# SCH_STAYAW_0_3_2024-05-15.net
KiCad netlist of a schematic drawn in EasyEDA
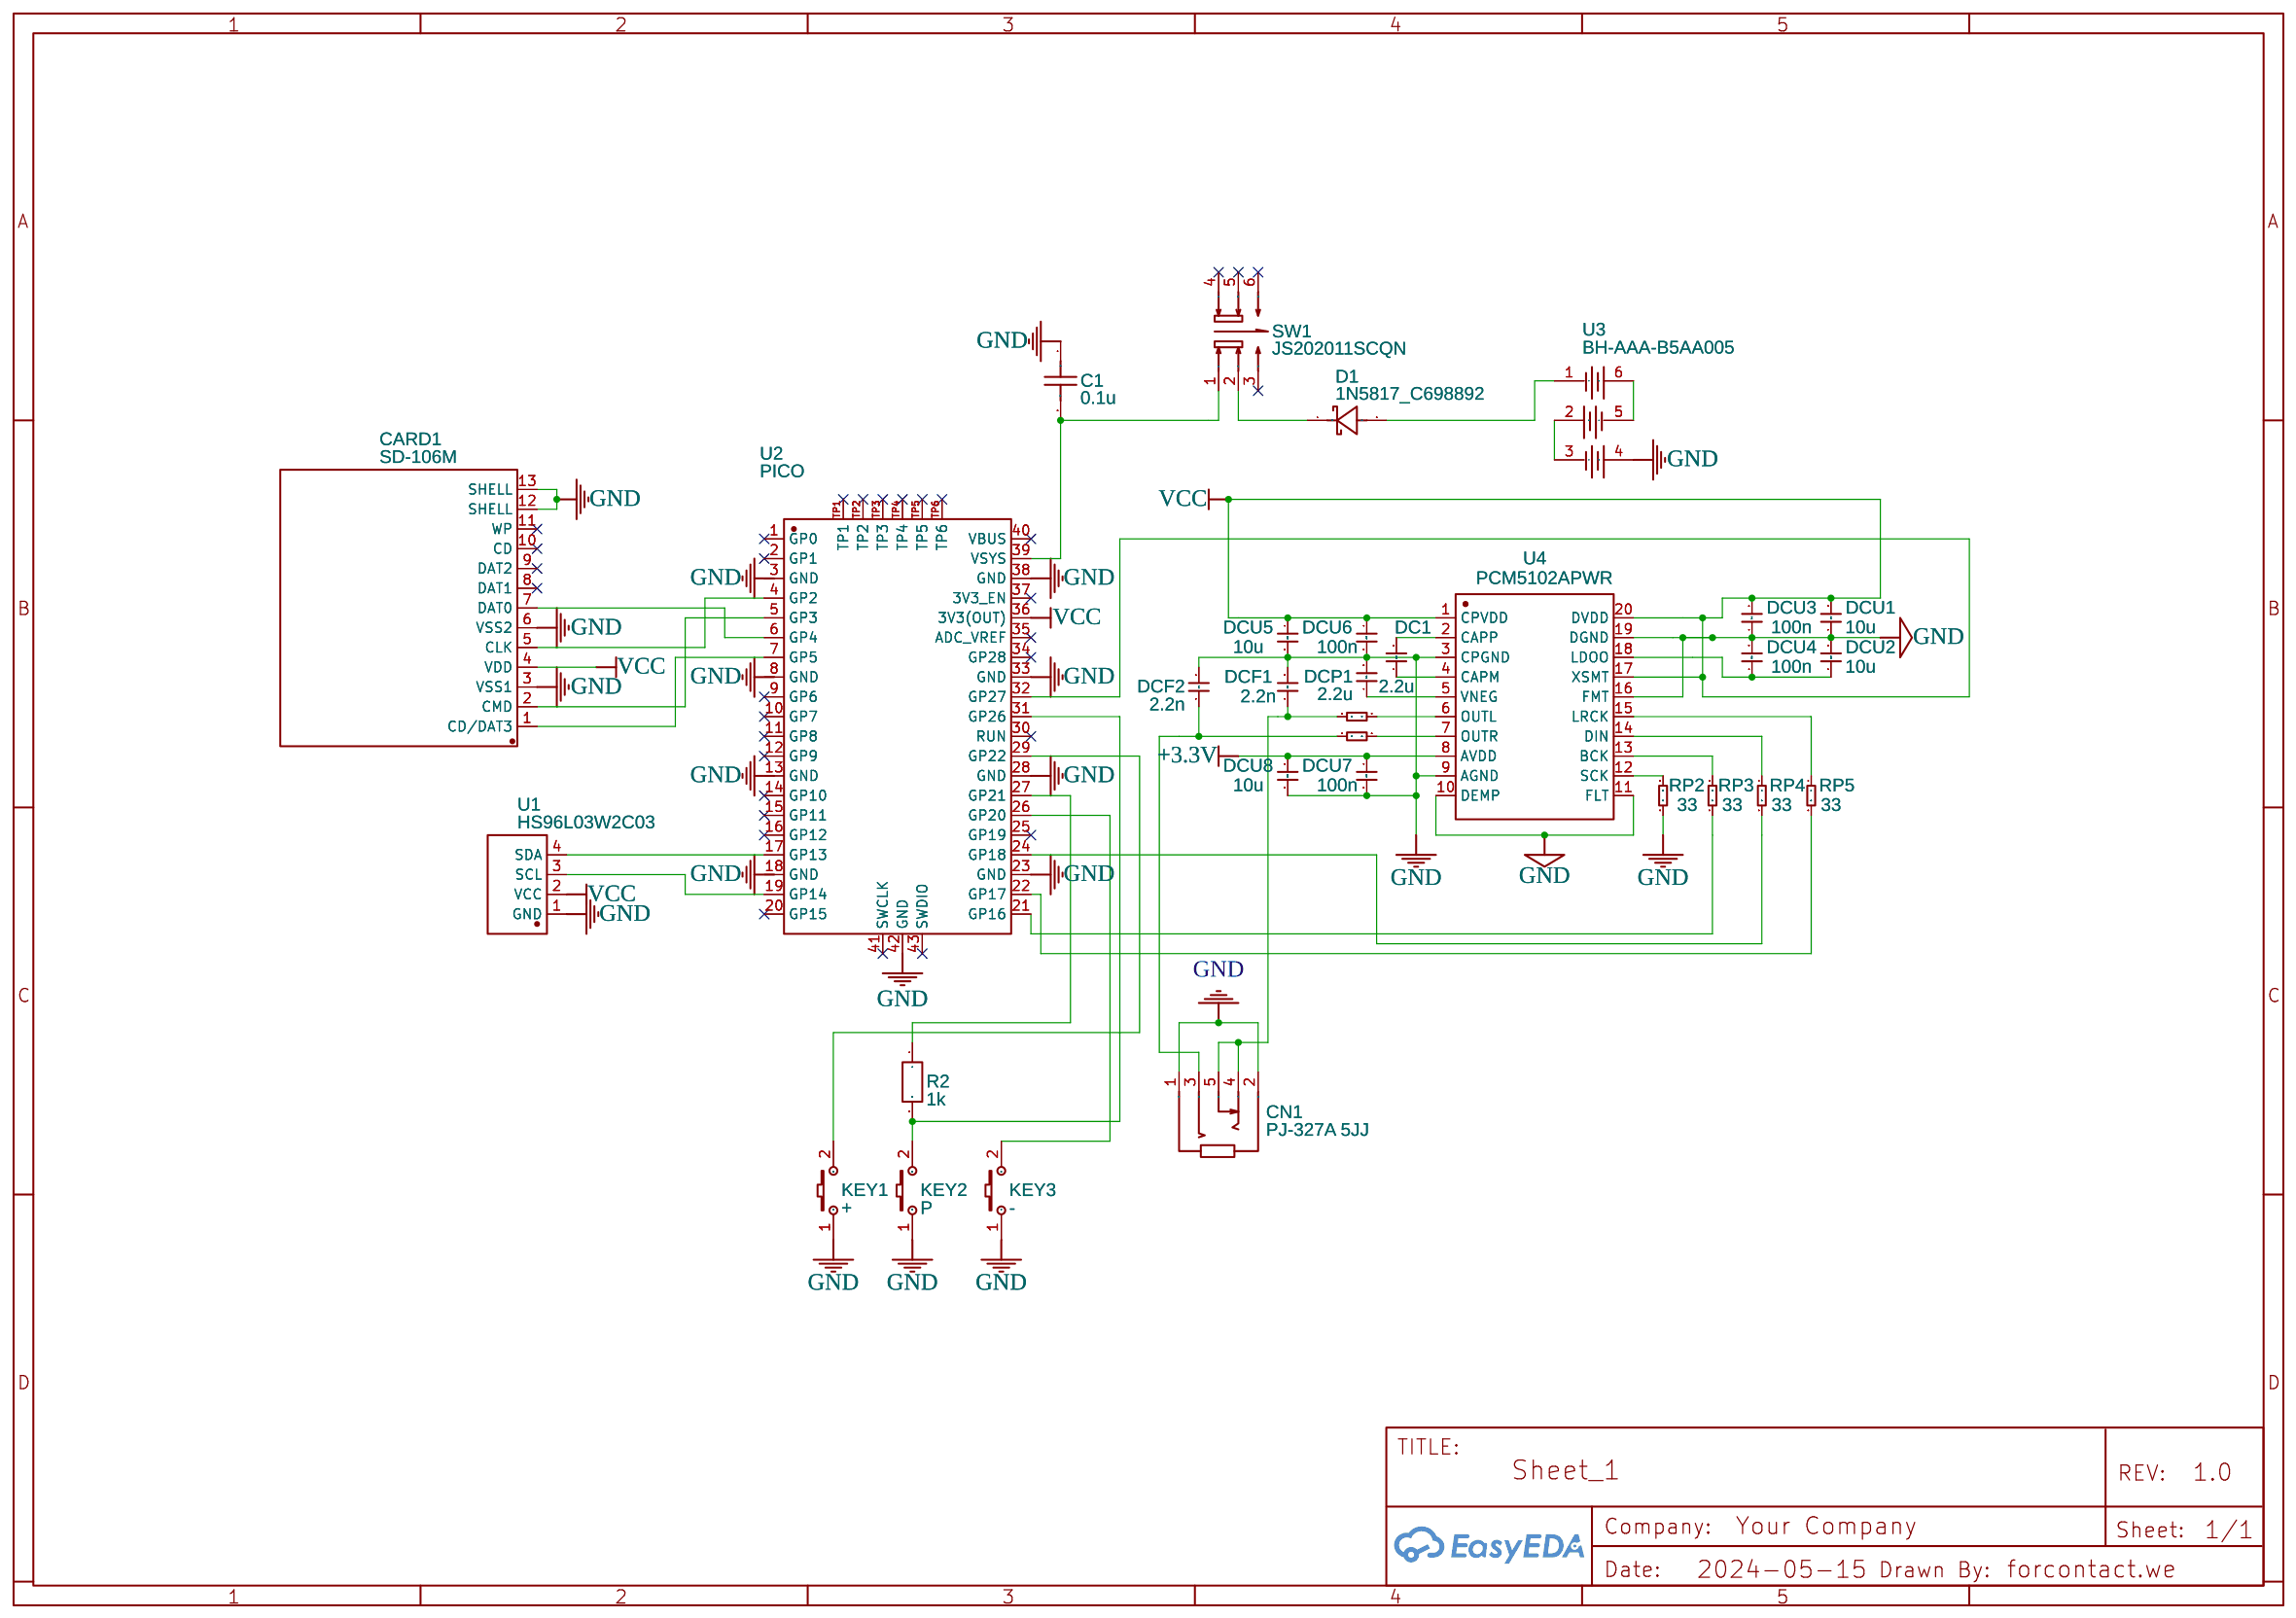
[diagram p0: schematic sheet]

(export (version "E")
  (design (tool "Eeschema 10.0.6"))
  (components
    (comp (ref "C1") (value "0.1u") (libsource (lib "") (part "C_0603_US")))
    (comp (ref "CARD1")
      (value "SD-106M")
      (fields (field (name "Manufacturer") "XUNPU(讯普)"))
      (libsource (lib "") (part "SD-106M"))
    )
    (comp (ref "CN1")
      (value "PJ-327A 5JJ")
      (fields (field (name "Manufacturer") "SHOU HAN(首韩)"))
      (libsource (lib "") (part "PJ-327A 5JJ"))
    )
    (comp (ref "D1")
      (value "1N5817_C698892")
      (fields (field (name "Manufacturer Part") "1N5817") (field (name "Manufacturer") "YANGJIE(扬杰)"))
      (libsource (lib "") (part "1N5817_C698892"))
    )
    (comp (ref "DC1")
      (value "2.2u")
      (fields (field (name "Manufacturer Part") "CL21B105KBFNNNE") (field (name "Manufacturer") "SAMSUNG"))
      (libsource (lib "") (part "Cap_0603_US_4"))
    )
    (comp (ref "DCF1")
      (value "2.2n")
      (fields (field (name "Manufacturer Part") "CL21A106KAYNNNE") (field (name "Manufacturer") "SAMSUNG"))
      (libsource (lib "") (part "Cap_0603_US_3"))
    )
    (comp (ref "DCF2")
      (value "2.2n")
      (fields (field (name "Manufacturer Part") "CL21A106KAYNNNE") (field (name "Manufacturer") "SAMSUNG"))
      (libsource (lib "") (part "Cap_0603_US_3"))
    )
    (comp (ref "DCP1")
      (value "2.2u")
      (fields (field (name "Manufacturer Part") "CL21B105KBFNNNE") (field (name "Manufacturer") "SAMSUNG"))
      (libsource (lib "") (part "Cap_0603_US_1"))
    )
    (comp (ref "DCU1")
      (value "10u")
      (fields (field (name "Manufacturer Part") "CL21A106KAYNNNE") (field (name "Manufacturer") "SAMSUNG"))
      (libsource (lib "") (part "Cap_0603_US"))
    )
    (comp (ref "DCU2")
      (value "10u")
      (fields (field (name "Manufacturer Part") "CL21A106KAYNNNE") (field (name "Manufacturer") "SAMSUNG"))
      (libsource (lib "") (part "Cap_0603_US"))
    )
    (comp (ref "DCU3")
      (value "100n")
      (fields (field (name "Manufacturer Part") "CL21A106KAYNNNE") (field (name "Manufacturer") "SAMSUNG"))
      (libsource (lib "") (part "Cap_0603_US"))
    )
    (comp (ref "DCU4")
      (value "100n")
      (fields (field (name "Manufacturer Part") "CL21A106KAYNNNE") (field (name "Manufacturer") "SAMSUNG"))
      (libsource (lib "") (part "Cap_0603_US"))
    )
    (comp (ref "DCU5")
      (value "10u")
      (fields (field (name "Manufacturer Part") "CL21A106KAYNNNE") (field (name "Manufacturer") "SAMSUNG"))
      (libsource (lib "") (part "Cap_0603_US_2"))
    )
    (comp (ref "DCU6")
      (value "100n")
      (fields (field (name "Manufacturer Part") "CL21A106KAYNNNE") (field (name "Manufacturer") "SAMSUNG"))
      (libsource (lib "") (part "Cap_0603_US_2"))
    )
    (comp (ref "DCU7")
      (value "100n")
      (fields (field (name "Manufacturer Part") "CL21A106KAYNNNE") (field (name "Manufacturer") "SAMSUNG"))
      (libsource (lib "") (part "Cap_0603_US_2"))
    )
    (comp (ref "DCU8")
      (value "10u")
      (fields (field (name "Manufacturer Part") "CL21A106KAYNNNE") (field (name "Manufacturer") "SAMSUNG"))
      (libsource (lib "") (part "Cap_0603_US_2"))
    )
    (comp (ref "DR1")
      (value "470")
      (fields (field (name "Manufacturer Part") "?"))
      (libsource (lib "") (part "Res_0603(1/10W)_EU_1"))
    )
    (comp (ref "DR2")
      (value "470")
      (fields (field (name "Manufacturer Part") "?"))
      (libsource (lib "") (part "Res_0603(1/10W)_EU_1"))
    )
    (comp (ref "KEY1")
      (value "+")
      (fields (field (name "Manufacturer Part") "K2-1107ST-A4SW-06"))
      (libsource (lib "") (part "K2-3.6×6.1_SMD"))
    )
    (comp (ref "KEY2")
      (value "P")
      (fields (field (name "Manufacturer Part") "K2-1107ST-A4SW-06"))
      (libsource (lib "") (part "K2-3.6×6.1_SMD"))
    )
    (comp (ref "KEY3")
      (value "-")
      (fields (field (name "Manufacturer Part") "K2-1107ST-A4SW-06"))
      (libsource (lib "") (part "K2-3.6×6.1_SMD"))
    )
    (comp (ref "R2") (value "1k") (libsource (lib "") (part "R_0603_EU")))
    (comp (ref "RP2")
      (value "33")
      (fields (field (name "Manufacturer Part") "?"))
      (libsource (lib "") (part "Res_0603(1/10W)_EU"))
    )
    (comp (ref "RP3")
      (value "33")
      (fields (field (name "Manufacturer Part") "?"))
      (libsource (lib "") (part "Res_0603(1/10W)_EU"))
    )
    (comp (ref "RP4")
      (value "33")
      (fields (field (name "Manufacturer Part") "?"))
      (libsource (lib "") (part "Res_0603(1/10W)_EU"))
    )
    (comp (ref "RP5")
      (value "33")
      (fields (field (name "Manufacturer Part") "?"))
      (libsource (lib "") (part "Res_0603(1/10W)_EU"))
    )
    (comp (ref "SW1")
      (value "JS202011SCQN")
      (fields (field (name "Manufacturer") "C&K"))
      (libsource (lib "") (part "JS202011SCQN"))
    )
    (comp (ref "U1")
      (value "HS96L03W2C03")
      (fields (field (name "Manufacturer") "HS(汉昇)"))
      (libsource (lib "") (part "HS96L03W2C03"))
    )
    (comp (ref "U2")
      (value "PICO")
      (fields (field (name "Manufacturer") "Raspberry Pi(树莓派)"))
      (libsource (lib "") (part "PICO"))
    )
    (comp (ref "U3")
      (value "BH-AAA-B5AA005")
      (fields (field (name "Manufacturer") "MYOUNG(美阳)"))
      (libsource (lib "") (part "BH-AAA-B5AA005"))
    )
    (comp (ref "U4")
      (value "PCM5102APWR")
      (fields (field (name "Manufacturer") "TI"))
      (libsource (lib "") (part "PCM5102APWR"))
    )
  )
  (nets
    (net (code "1") (name "+3.3V") (class "Default")
      (node (ref "DCU7") (pin "1") (pinfunction "1_1") (pintype "unspecified"))
      (node (ref "DCU8") (pin "1") (pinfunction "1_1") (pintype "unspecified"))
      (node (ref "U4") (pin "8") (pinfunction "AVDD_8") (pintype "unspecified"))
    )
    (net (code "2") (name "GND") (class "Default")
      (node (ref "C1") (pin "1") (pinfunction "1_1") (pintype "unspecified"))
      (node (ref "CARD1") (pin "12") (pinfunction "SHELL_12") (pintype "unspecified"))
      (node (ref "CARD1") (pin "13") (pinfunction "SHELL_13") (pintype "unspecified"))
      (node (ref "CARD1") (pin "3") (pinfunction "VSS1_3") (pintype "unspecified"))
      (node (ref "CARD1") (pin "6") (pinfunction "VSS2_6") (pintype "unspecified"))
      (node (ref "CN1") (pin "1") (pinfunction "1_1") (pintype "unspecified"))
      (node (ref "CN1") (pin "2") (pinfunction "2_2") (pintype "unspecified"))
      (node (ref "DCF1") (pin "2") (pinfunction "2_2") (pintype "unspecified"))
      (node (ref "DCF2") (pin "2") (pinfunction "2_2") (pintype "unspecified"))
      (node (ref "DCP1") (pin "2") (pinfunction "2_2") (pintype "unspecified"))
      (node (ref "DCU1") (pin "1") (pinfunction "1_1") (pintype "unspecified"))
      (node (ref "DCU2") (pin "2") (pinfunction "2_2") (pintype "unspecified"))
      (node (ref "DCU3") (pin "1") (pinfunction "1_1") (pintype "unspecified"))
      (node (ref "DCU4") (pin "2") (pinfunction "2_2") (pintype "unspecified"))
      (node (ref "DCU5") (pin "2") (pinfunction "2_2") (pintype "unspecified"))
      (node (ref "DCU6") (pin "2") (pinfunction "2_2") (pintype "unspecified"))
      (node (ref "DCU7") (pin "2") (pinfunction "2_2") (pintype "unspecified"))
      (node (ref "DCU8") (pin "2") (pinfunction "2_2") (pintype "unspecified"))
      (node (ref "KEY1") (pin "1") (pinfunction "1_1") (pintype "unspecified"))
      (node (ref "KEY2") (pin "1") (pinfunction "1_1") (pintype "unspecified"))
      (node (ref "KEY3") (pin "1") (pinfunction "1_1") (pintype "unspecified"))
      (node (ref "RP2") (pin "2") (pinfunction "2_2") (pintype "unspecified"))
      (node (ref "U1") (pin "1") (pinfunction "GND_1") (pintype "unspecified"))
      (node (ref "U2") (pin "13") (pinfunction "GND_13") (pintype "unspecified"))
      (node (ref "U2") (pin "18") (pinfunction "GND_18") (pintype "unspecified"))
      (node (ref "U2") (pin "23") (pinfunction "GND_23") (pintype "unspecified"))
      (node (ref "U2") (pin "28") (pinfunction "GND_28") (pintype "unspecified"))
      (node (ref "U2") (pin "3") (pinfunction "GND_3") (pintype "unspecified"))
      (node (ref "U2") (pin "33") (pinfunction "GND_33") (pintype "unspecified"))
      (node (ref "U2") (pin "38") (pinfunction "GND_38") (pintype "unspecified"))
      (node (ref "U2") (pin "42") (pinfunction "GND_42") (pintype "unspecified"))
      (node (ref "U2") (pin "8") (pinfunction "GND_8") (pintype "unspecified"))
      (node (ref "U3") (pin "4") (pinfunction "+_4") (pintype "input"))
      (node (ref "U4") (pin "10") (pinfunction "DEMP_10") (pintype "unspecified"))
      (node (ref "U4") (pin "11") (pinfunction "FLT_11") (pintype "unspecified"))
      (node (ref "U4") (pin "16") (pinfunction "FMT_16") (pintype "unspecified"))
      (node (ref "U4") (pin "19") (pinfunction "DGND_19") (pintype "unspecified"))
      (node (ref "U4") (pin "3") (pinfunction "CPGND_3") (pintype "unspecified"))
      (node (ref "U4") (pin "9") (pinfunction "AGND_9") (pintype "unspecified"))
    )
    (net (code "3") (name "Net-(CARD1-CD{slash}DAT3)") (class "Default")
      (node (ref "CARD1") (pin "1") (pinfunction "CD/DAT3_1") (pintype "unspecified"))
      (node (ref "U2") (pin "7") (pinfunction "GP5_7") (pintype "unspecified"))
    )
    (net (code "4") (name "Net-(CARD1-CLK)") (class "Default")
      (node (ref "CARD1") (pin "5") (pinfunction "CLK_5") (pintype "unspecified"))
      (node (ref "U2") (pin "4") (pinfunction "GP2_4") (pintype "unspecified"))
    )
    (net (code "5") (name "Net-(CARD1-CMD)") (class "Default")
      (node (ref "CARD1") (pin "2") (pinfunction "CMD_2") (pintype "unspecified"))
      (node (ref "U2") (pin "5") (pinfunction "GP3_5") (pintype "unspecified"))
    )
    (net (code "6") (name "Net-(CARD1-DAT0)") (class "Default")
      (node (ref "CARD1") (pin "7") (pinfunction "DAT0_7") (pintype "unspecified"))
      (node (ref "U2") (pin "6") (pinfunction "GP4_6") (pintype "unspecified"))
    )
    (net (code "7") (name "Net-(CN1-Pad3)") (class "Default")
      (node (ref "CN1") (pin "3") (pinfunction "3_3") (pintype "unspecified"))
      (node (ref "DCF2") (pin "1") (pinfunction "1_1") (pintype "unspecified"))
      (node (ref "DR1") (pin "1") (pinfunction "1_1") (pintype "unspecified"))
    )
    (net (code "8") (name "Net-(CN1-Pad4)") (class "Default")
      (node (ref "CN1") (pin "4") (pinfunction "4_4") (pintype "unspecified"))
      (node (ref "CN1") (pin "5") (pinfunction "5_5") (pintype "unspecified"))
      (node (ref "DCF1") (pin "1") (pinfunction "1_1") (pintype "unspecified"))
      (node (ref "DR2") (pin "1") (pinfunction "1_1") (pintype "unspecified"))
    )
    (net (code "9") (name "Net-(D1-Pad1)") (class "Default")
      (node (ref "D1") (pin "1") (pinfunction "1_1") (pintype "unspecified"))
      (node (ref "SW1") (pin "2") (pinfunction "2_2") (pintype "unspecified"))
    )
    (net (code "10") (name "Net-(D1-Pad2)") (class "Default")
      (node (ref "D1") (pin "2") (pinfunction "2_2") (pintype "unspecified"))
      (node (ref "U3") (pin "1") (pinfunction "-_1") (pintype "input"))
    )
    (net (code "11") (name "Net-(U1-SCL)") (class "Default")
      (node (ref "U1") (pin "3") (pinfunction "SCL_3") (pintype "unspecified"))
      (node (ref "U2") (pin "19") (pinfunction "GP14_19") (pintype "unspecified"))
    )
    (net (code "12") (name "Net-(U1-SDA)") (class "Default")
      (node (ref "U1") (pin "4") (pinfunction "SDA_4") (pintype "unspecified"))
      (node (ref "U2") (pin "17") (pinfunction "GP13_17") (pintype "unspecified"))
    )
    (net (code "13") (name "Net-(U2-GP16)") (class "Default")
      (node (ref "RP3") (pin "2") (pinfunction "2_2") (pintype "unspecified"))
      (node (ref "U2") (pin "21") (pinfunction "GP16_21") (pintype "unspecified"))
    )
    (net (code "14") (name "Net-(U2-GP17)") (class "Default")
      (node (ref "RP5") (pin "2") (pinfunction "2_2") (pintype "unspecified"))
      (node (ref "U2") (pin "22") (pinfunction "GP17_22") (pintype "unspecified"))
    )
    (net (code "15") (name "Net-(U2-GP18)") (class "Default")
      (node (ref "RP4") (pin "2") (pinfunction "2_2") (pintype "unspecified"))
      (node (ref "U2") (pin "24") (pinfunction "GP18_24") (pintype "unspecified"))
    )
    (net (code "16") (name "Net-(U2-GP20)") (class "Default")
      (node (ref "KEY3") (pin "2") (pinfunction "2_2") (pintype "unspecified"))
      (node (ref "U2") (pin "26") (pinfunction "GP20_26") (pintype "unspecified"))
    )
    (net (code "17") (name "Net-(U2-GP21)") (class "Default")
      (node (ref "R2") (pin "1") (pinfunction "1_1") (pintype "unspecified"))
      (node (ref "U2") (pin "27") (pinfunction "GP21_27") (pintype "unspecified"))
    )
    (net (code "18") (name "Net-(U2-GP22)") (class "Default")
      (node (ref "KEY1") (pin "2") (pinfunction "2_2") (pintype "unspecified"))
      (node (ref "U2") (pin "29") (pinfunction "GP22_29") (pintype "unspecified"))
    )
    (net (code "19") (name "Net-(U2-GP26)") (class "Default")
      (node (ref "KEY2") (pin "2") (pinfunction "2_2") (pintype "unspecified"))
      (node (ref "R2") (pin "2") (pinfunction "2_2") (pintype "unspecified"))
      (node (ref "U2") (pin "31") (pinfunction "GP26_31") (pintype "unspecified"))
    )
    (net (code "20") (name "Net-(U2-VSYS)") (class "Default")
      (node (ref "C1") (pin "2") (pinfunction "2_2") (pintype "unspecified"))
      (node (ref "SW1") (pin "1") (pinfunction "1_1") (pintype "unspecified"))
      (node (ref "U2") (pin "39") (pinfunction "VSYS_39") (pintype "unspecified"))
    )
    (net (code "21") (name "Net-(U3-+-Pad2)") (class "Default")
      (node (ref "U3") (pin "2") (pinfunction "+_2") (pintype "input"))
      (node (ref "U3") (pin "3") (pinfunction "-_3") (pintype "input"))
    )
    (net (code "22") (name "Net-(U3-+-Pad6)") (class "Default")
      (node (ref "U3") (pin "5") (pinfunction "-_5") (pintype "input"))
      (node (ref "U3") (pin "6") (pinfunction "+_6") (pintype "input"))
    )
    (net (code "23") (name "Net-(U4-BCK)") (class "Default")
      (node (ref "RP3") (pin "1") (pinfunction "1_1") (pintype "unspecified"))
      (node (ref "U4") (pin "13") (pinfunction "BCK_13") (pintype "unspecified"))
    )
    (net (code "24") (name "Net-(U4-CAPM)") (class "Default")
      (node (ref "DC1") (pin "1") (pinfunction "1_1") (pintype "unspecified"))
      (node (ref "U4") (pin "4") (pinfunction "CAPM_4") (pintype "unspecified"))
    )
    (net (code "25") (name "Net-(U4-CAPP)") (class "Default")
      (node (ref "DC1") (pin "2") (pinfunction "2_2") (pintype "unspecified"))
      (node (ref "U4") (pin "2") (pinfunction "CAPP_2") (pintype "unspecified"))
    )
    (net (code "26") (name "Net-(U4-DIN)") (class "Default")
      (node (ref "RP4") (pin "1") (pinfunction "1_1") (pintype "unspecified"))
      (node (ref "U4") (pin "14") (pinfunction "DIN_14") (pintype "unspecified"))
    )
    (net (code "27") (name "Net-(U4-LDOO)") (class "Default")
      (node (ref "DCU2") (pin "1") (pinfunction "1_1") (pintype "unspecified"))
      (node (ref "DCU4") (pin "1") (pinfunction "1_1") (pintype "unspecified"))
      (node (ref "U4") (pin "18") (pinfunction "LDOO_18") (pintype "unspecified"))
    )
    (net (code "28") (name "Net-(U4-LRCK)") (class "Default")
      (node (ref "RP5") (pin "1") (pinfunction "1_1") (pintype "unspecified"))
      (node (ref "U4") (pin "15") (pinfunction "LRCK_15") (pintype "unspecified"))
    )
    (net (code "29") (name "Net-(U4-OUTL)") (class "Default")
      (node (ref "DR2") (pin "2") (pinfunction "2_2") (pintype "unspecified"))
      (node (ref "U4") (pin "6") (pinfunction "OUTL_6") (pintype "unspecified"))
    )
    (net (code "30") (name "Net-(U4-OUTR)") (class "Default")
      (node (ref "DR1") (pin "2") (pinfunction "2_2") (pintype "unspecified"))
      (node (ref "U4") (pin "7") (pinfunction "OUTR_7") (pintype "unspecified"))
    )
    (net (code "31") (name "Net-(U4-SCK)") (class "Default")
      (node (ref "RP2") (pin "1") (pinfunction "1_1") (pintype "unspecified"))
      (node (ref "U4") (pin "12") (pinfunction "SCK_12") (pintype "unspecified"))
    )
    (net (code "32") (name "Net-(U4-VNEG)") (class "Default")
      (node (ref "DCP1") (pin "1") (pinfunction "1_1") (pintype "unspecified"))
      (node (ref "U4") (pin "5") (pinfunction "VNEG_5") (pintype "unspecified"))
    )
    (net (code "33") (name "VCC") (class "Default")
      (node (ref "CARD1") (pin "4") (pinfunction "VDD_4") (pintype "unspecified"))
      (node (ref "DCU1") (pin "2") (pinfunction "2_2") (pintype "unspecified"))
      (node (ref "DCU3") (pin "2") (pinfunction "2_2") (pintype "unspecified"))
      (node (ref "DCU5") (pin "1") (pinfunction "1_1") (pintype "unspecified"))
      (node (ref "DCU6") (pin "1") (pinfunction "1_1") (pintype "unspecified"))
      (node (ref "U1") (pin "2") (pinfunction "VCC_2") (pintype "unspecified"))
      (node (ref "U2") (pin "32") (pinfunction "GP27_32") (pintype "unspecified"))
      (node (ref "U2") (pin "36") (pinfunction "3V3(OUT)_36") (pintype "unspecified"))
      (node (ref "U4") (pin "1") (pinfunction "CPVDD_1") (pintype "unspecified"))
      (node (ref "U4") (pin "17") (pinfunction "XSMT_17") (pintype "unspecified"))
      (node (ref "U4") (pin "20") (pinfunction "DVDD_20") (pintype "unspecified"))
    )
    (net (code "34") (name "unconnected-(CARD1-CD-Pad10)") (class "Default")
      (node (ref "CARD1") (pin "10") (pinfunction "CD_10") (pintype "unspecified+no_connect"))
    )
    (net (code "35") (name "unconnected-(CARD1-DAT1-Pad8)") (class "Default")
      (node (ref "CARD1") (pin "8") (pinfunction "DAT1_8") (pintype "unspecified+no_connect"))
    )
    (net (code "36") (name "unconnected-(CARD1-DAT2-Pad9)") (class "Default")
      (node (ref "CARD1") (pin "9") (pinfunction "DAT2_9") (pintype "unspecified+no_connect"))
    )
    (net (code "37") (name "unconnected-(CARD1-WP-Pad11)") (class "Default")
      (node (ref "CARD1") (pin "11") (pinfunction "WP_11") (pintype "unspecified+no_connect"))
    )
    (net (code "38") (name "unconnected-(SW1-Pad3)") (class "Default")
      (node (ref "SW1") (pin "3") (pinfunction "3_3") (pintype "unspecified+no_connect"))
    )
    (net (code "39") (name "unconnected-(SW1-Pad4)") (class "Default")
      (node (ref "SW1") (pin "4") (pinfunction "4_4") (pintype "unspecified+no_connect"))
    )
    (net (code "40") (name "unconnected-(SW1-Pad5)") (class "Default")
      (node (ref "SW1") (pin "5") (pinfunction "5_5") (pintype "unspecified+no_connect"))
    )
    (net (code "41") (name "unconnected-(SW1-Pad6)") (class "Default")
      (node (ref "SW1") (pin "6") (pinfunction "6_6") (pintype "unspecified+no_connect"))
    )
    (net (code "42") (name "unconnected-(U2-3V3_EN-Pad37)") (class "Default")
      (node (ref "U2") (pin "37") (pinfunction "3V3_EN_37") (pintype "unspecified+no_connect"))
    )
    (net (code "43") (name "unconnected-(U2-ADC_VREF-Pad35)") (class "Default")
      (node (ref "U2") (pin "35") (pinfunction "ADC_VREF_35") (pintype "unspecified+no_connect"))
    )
    (net (code "44") (name "unconnected-(U2-GP0-Pad1)") (class "Default")
      (node (ref "U2") (pin "1") (pinfunction "GP0_1") (pintype "unspecified+no_connect"))
    )
    (net (code "45") (name "unconnected-(U2-GP1-Pad2)") (class "Default")
      (node (ref "U2") (pin "2") (pinfunction "GP1_2") (pintype "unspecified+no_connect"))
    )
    (net (code "46") (name "unconnected-(U2-GP6-Pad9)") (class "Default")
      (node (ref "U2") (pin "9") (pinfunction "GP6_9") (pintype "unspecified+no_connect"))
    )
    (net (code "47") (name "unconnected-(U2-GP7-Pad10)") (class "Default")
      (node (ref "U2") (pin "10") (pinfunction "GP7_10") (pintype "unspecified+no_connect"))
    )
    (net (code "48") (name "unconnected-(U2-GP8-Pad11)") (class "Default")
      (node (ref "U2") (pin "11") (pinfunction "GP8_11") (pintype "unspecified+no_connect"))
    )
    (net (code "49") (name "unconnected-(U2-GP9-Pad12)") (class "Default")
      (node (ref "U2") (pin "12") (pinfunction "GP9_12") (pintype "unspecified+no_connect"))
    )
    (net (code "50") (name "unconnected-(U2-GP10-Pad14)") (class "Default")
      (node (ref "U2") (pin "14") (pinfunction "GP10_14") (pintype "unspecified+no_connect"))
    )
    (net (code "51") (name "unconnected-(U2-GP11-Pad15)") (class "Default")
      (node (ref "U2") (pin "15") (pinfunction "GP11_15") (pintype "unspecified+no_connect"))
    )
    (net (code "52") (name "unconnected-(U2-GP12-Pad16)") (class "Default")
      (node (ref "U2") (pin "16") (pinfunction "GP12_16") (pintype "unspecified+no_connect"))
    )
    (net (code "53") (name "unconnected-(U2-GP15-Pad20)") (class "Default")
      (node (ref "U2") (pin "20") (pinfunction "GP15_20") (pintype "unspecified+no_connect"))
    )
    (net (code "54") (name "unconnected-(U2-GP19-Pad25)") (class "Default")
      (node (ref "U2") (pin "25") (pinfunction "GP19_25") (pintype "unspecified+no_connect"))
    )
    (net (code "55") (name "unconnected-(U2-GP28-Pad34)") (class "Default")
      (node (ref "U2") (pin "34") (pinfunction "GP28_34") (pintype "unspecified+no_connect"))
    )
    (net (code "56") (name "unconnected-(U2-PadTP1)") (class "Default")
      (node (ref "U2") (pin "TP1") (pinfunction "TP1_TP1") (pintype "unspecified+no_connect"))
    )
    (net (code "57") (name "unconnected-(U2-PadTP2)") (class "Default")
      (node (ref "U2") (pin "TP2") (pinfunction "TP2_TP2") (pintype "unspecified+no_connect"))
    )
    (net (code "58") (name "unconnected-(U2-PadTP3)") (class "Default")
      (node (ref "U2") (pin "TP3") (pinfunction "TP3_TP3") (pintype "unspecified+no_connect"))
    )
    (net (code "59") (name "unconnected-(U2-PadTP4)") (class "Default")
      (node (ref "U2") (pin "TP4") (pinfunction "TP4_TP4") (pintype "unspecified+no_connect"))
    )
    (net (code "60") (name "unconnected-(U2-PadTP5)") (class "Default")
      (node (ref "U2") (pin "TP5") (pinfunction "TP5_TP5") (pintype "unspecified+no_connect"))
    )
    (net (code "61") (name "unconnected-(U2-PadTP6)") (class "Default")
      (node (ref "U2") (pin "TP6") (pinfunction "TP6_TP6") (pintype "unspecified+no_connect"))
    )
    (net (code "62") (name "unconnected-(U2-RUN-Pad30)") (class "Default")
      (node (ref "U2") (pin "30") (pinfunction "RUN_30") (pintype "unspecified+no_connect"))
    )
    (net (code "63") (name "unconnected-(U2-SWCLK-Pad41)") (class "Default")
      (node (ref "U2") (pin "41") (pinfunction "SWCLK_41") (pintype "unspecified+no_connect"))
    )
    (net (code "64") (name "unconnected-(U2-SWDIO-Pad43)") (class "Default")
      (node (ref "U2") (pin "43") (pinfunction "SWDIO_43") (pintype "unspecified+no_connect"))
    )
    (net (code "65") (name "unconnected-(U2-VBUS-Pad40)") (class "Default")
      (node (ref "U2") (pin "40") (pinfunction "VBUS_40") (pintype "unspecified+no_connect"))
    )
  )
)
